# Distance_Sensors.net
KiCad netlist of a schematic drawn in Altium Designer
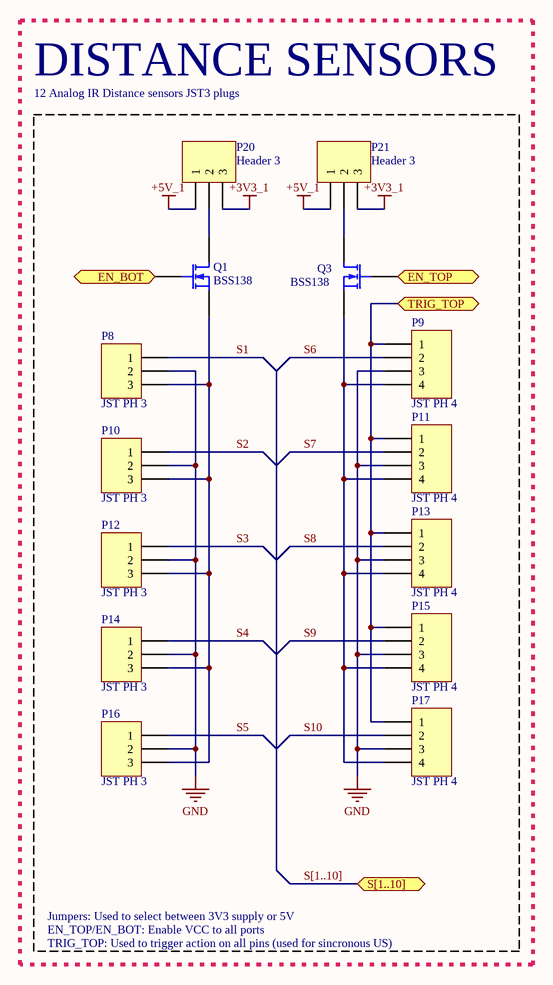
[diagram p0: Distance Sensors.SchDoc]

(export (version "E")
  (design (tool "Eeschema 10.0.6"))
  (components
    (comp (ref "P8")
      (value "JST PH 3")
      (footprint "B3B-PH-K")
      (libsource (lib "CustomLibrary") (part "JST PH 3"))
    )
    (comp (ref "P9")
      (value "JST PH 4")
      (footprint "B4B-PH-K")
      (libsource (lib "CustomLibrary") (part "JST PH 4"))
    )
    (comp (ref "P10")
      (value "JST PH 3")
      (footprint "B3B-PH-K")
      (libsource (lib "CustomLibrary") (part "JST PH 3"))
    )
    (comp (ref "P11")
      (value "JST PH 4")
      (footprint "B4B-PH-K")
      (libsource (lib "CustomLibrary") (part "JST PH 4"))
    )
    (comp (ref "P12")
      (value "JST PH 3")
      (footprint "B3B-PH-K")
      (libsource (lib "CustomLibrary") (part "JST PH 3"))
    )
    (comp (ref "P13")
      (value "JST PH 4")
      (footprint "B4B-PH-K")
      (libsource (lib "CustomLibrary") (part "JST PH 4"))
    )
    (comp (ref "P14")
      (value "JST PH 3")
      (footprint "B3B-PH-K")
      (libsource (lib "CustomLibrary") (part "JST PH 3"))
    )
    (comp (ref "P15")
      (value "JST PH 4")
      (footprint "B4B-PH-K")
      (libsource (lib "CustomLibrary") (part "JST PH 4"))
    )
    (comp (ref "P16")
      (value "JST PH 3")
      (footprint "B3B-PH-K")
      (libsource (lib "CustomLibrary") (part "JST PH 3"))
    )
    (comp (ref "P17")
      (value "JST PH 4")
      (footprint "B4B-PH-K")
      (libsource (lib "CustomLibrary") (part "JST PH 4"))
    )
    (comp (ref "P20")
      (value "Header 3")
      (footprint "HDR1X3")
      (description "Header, 3-Pin")
      (fields (field (name "PUBLISHER") "Altium Limited"))
      (libsource (lib "Miscellaneous Connectors") (part "Header 3"))
    )
    (comp (ref "P21")
      (value "Header 3")
      (footprint "HDR1X3")
      (description "Header, 3-Pin")
      (fields (field (name "PUBLISHER") "Altium Limited"))
      (libsource (lib "Miscellaneous Connectors") (part "Header 3"))
    )
    (comp (ref "Q1")
      (value "BSS138")
      (footprint "SOT23")
      (description "N-Channel Enhancement Mode Vertical DMOS FET")
      (fields (field (name "PUBLISHER") "Altium Limited"))
      (libsource (lib "Zetex Discrete MOSFET") (part "BSS138"))
    )
    (comp (ref "Q3")
      (value "BSS138")
      (footprint "SOT23")
      (description "N-Channel Enhancement Mode Vertical DMOS FET")
      (fields (field (name "PUBLISHER") "Altium Limited"))
      (libsource (lib "Zetex Discrete MOSFET") (part "BSS138"))
    )
  )
  (nets
    (net (code "1") (name "+3V3_1") (class "Default")
      (node (ref "P20") (pin "3") (pinfunction "3_3") (pintype "passive"))
      (node (ref "P21") (pin "3") (pinfunction "3_3") (pintype "passive"))
    )
    (net (code "2") (name "+5V_1") (class "Default")
      (node (ref "P20") (pin "1") (pinfunction "1_1") (pintype "passive"))
      (node (ref "P21") (pin "1") (pinfunction "1_1") (pintype "passive"))
    )
    (net (code "3") (name "/EN_BOT") (class "Default")
      (node (ref "Q1") (pin "3") (pinfunction "G_3") (pintype "passive"))
    )
    (net (code "4") (name "/EN_TOP") (class "Default")
      (node (ref "Q3") (pin "3") (pinfunction "G_3") (pintype "passive"))
    )
    (net (code "5") (name "/S1") (class "Default")
      (node (ref "P8") (pin "1") (pinfunction "1_1") (pintype "passive"))
    )
    (net (code "6") (name "/S2") (class "Default")
      (node (ref "P10") (pin "1") (pinfunction "1_1") (pintype "passive"))
    )
    (net (code "7") (name "/S3") (class "Default")
      (node (ref "P12") (pin "1") (pinfunction "1_1") (pintype "passive"))
    )
    (net (code "8") (name "/S4") (class "Default")
      (node (ref "P14") (pin "1") (pinfunction "1_1") (pintype "passive"))
    )
    (net (code "9") (name "/S5") (class "Default")
      (node (ref "P16") (pin "1") (pinfunction "1_1") (pintype "passive"))
    )
    (net (code "10") (name "/S6") (class "Default")
      (node (ref "P9") (pin "2") (pinfunction "2_2") (pintype "passive"))
    )
    (net (code "11") (name "/S7") (class "Default")
      (node (ref "P11") (pin "2") (pinfunction "2_2") (pintype "passive"))
    )
    (net (code "12") (name "/S8") (class "Default")
      (node (ref "P13") (pin "2") (pinfunction "2_2") (pintype "passive"))
    )
    (net (code "13") (name "/S9") (class "Default")
      (node (ref "P15") (pin "2") (pinfunction "2_2") (pintype "passive"))
    )
    (net (code "14") (name "/S10") (class "Default")
      (node (ref "P17") (pin "2") (pinfunction "2_2") (pintype "passive"))
    )
    (net (code "16") (name "/TRIG_TOP") (class "Default")
      (node (ref "P11") (pin "1") (pinfunction "1_1") (pintype "passive"))
      (node (ref "P13") (pin "1") (pinfunction "1_1") (pintype "passive"))
      (node (ref "P15") (pin "1") (pinfunction "1_1") (pintype "passive"))
      (node (ref "P17") (pin "1") (pinfunction "1_1") (pintype "passive"))
      (node (ref "P9") (pin "1") (pinfunction "1_1") (pintype "passive"))
    )
    (net (code "17") (name "GND") (class "Default")
      (node (ref "P10") (pin "2") (pinfunction "2_2") (pintype "passive"))
      (node (ref "P11") (pin "3") (pinfunction "3_3") (pintype "passive"))
      (node (ref "P12") (pin "2") (pinfunction "2_2") (pintype "passive"))
      (node (ref "P13") (pin "3") (pinfunction "3_3") (pintype "passive"))
      (node (ref "P14") (pin "2") (pinfunction "2_2") (pintype "passive"))
      (node (ref "P15") (pin "3") (pinfunction "3_3") (pintype "passive"))
      (node (ref "P16") (pin "2") (pinfunction "2_2") (pintype "passive"))
      (node (ref "P17") (pin "3") (pinfunction "3_3") (pintype "passive"))
      (node (ref "P8") (pin "2") (pinfunction "2_2") (pintype "passive"))
      (node (ref "P9") (pin "3") (pinfunction "3_3") (pintype "passive"))
    )
    (net (code "18") (name "Net-(Q1-D)") (class "Default")
      (node (ref "P20") (pin "2") (pinfunction "2_2") (pintype "passive"))
      (node (ref "Q1") (pin "1") (pinfunction "D_1") (pintype "passive"))
    )
    (net (code "19") (name "Net-(Q1-S)") (class "Default")
      (node (ref "P10") (pin "3") (pinfunction "3_3") (pintype "passive"))
      (node (ref "P12") (pin "3") (pinfunction "3_3") (pintype "passive"))
      (node (ref "P14") (pin "3") (pinfunction "3_3") (pintype "passive"))
      (node (ref "P16") (pin "3") (pinfunction "3_3") (pintype "passive"))
      (node (ref "P8") (pin "3") (pinfunction "3_3") (pintype "passive"))
      (node (ref "Q1") (pin "2") (pinfunction "S_2") (pintype "passive"))
    )
    (net (code "20") (name "Net-(Q3-D)") (class "Default")
      (node (ref "P21") (pin "2") (pinfunction "2_2") (pintype "passive"))
      (node (ref "Q3") (pin "1") (pinfunction "D_1") (pintype "passive"))
    )
    (net (code "21") (name "Net-(Q3-S)") (class "Default")
      (node (ref "P11") (pin "4") (pinfunction "4_4") (pintype "passive"))
      (node (ref "P13") (pin "4") (pinfunction "4_4") (pintype "passive"))
      (node (ref "P15") (pin "4") (pinfunction "4_4") (pintype "passive"))
      (node (ref "P17") (pin "4") (pinfunction "4_4") (pintype "passive"))
      (node (ref "P9") (pin "4") (pinfunction "4_4") (pintype "passive"))
      (node (ref "Q3") (pin "2") (pinfunction "S_2") (pintype "passive"))
    )
  )
)
